# combined.net
KiCad netlist of a schematic drawn in EAGLE
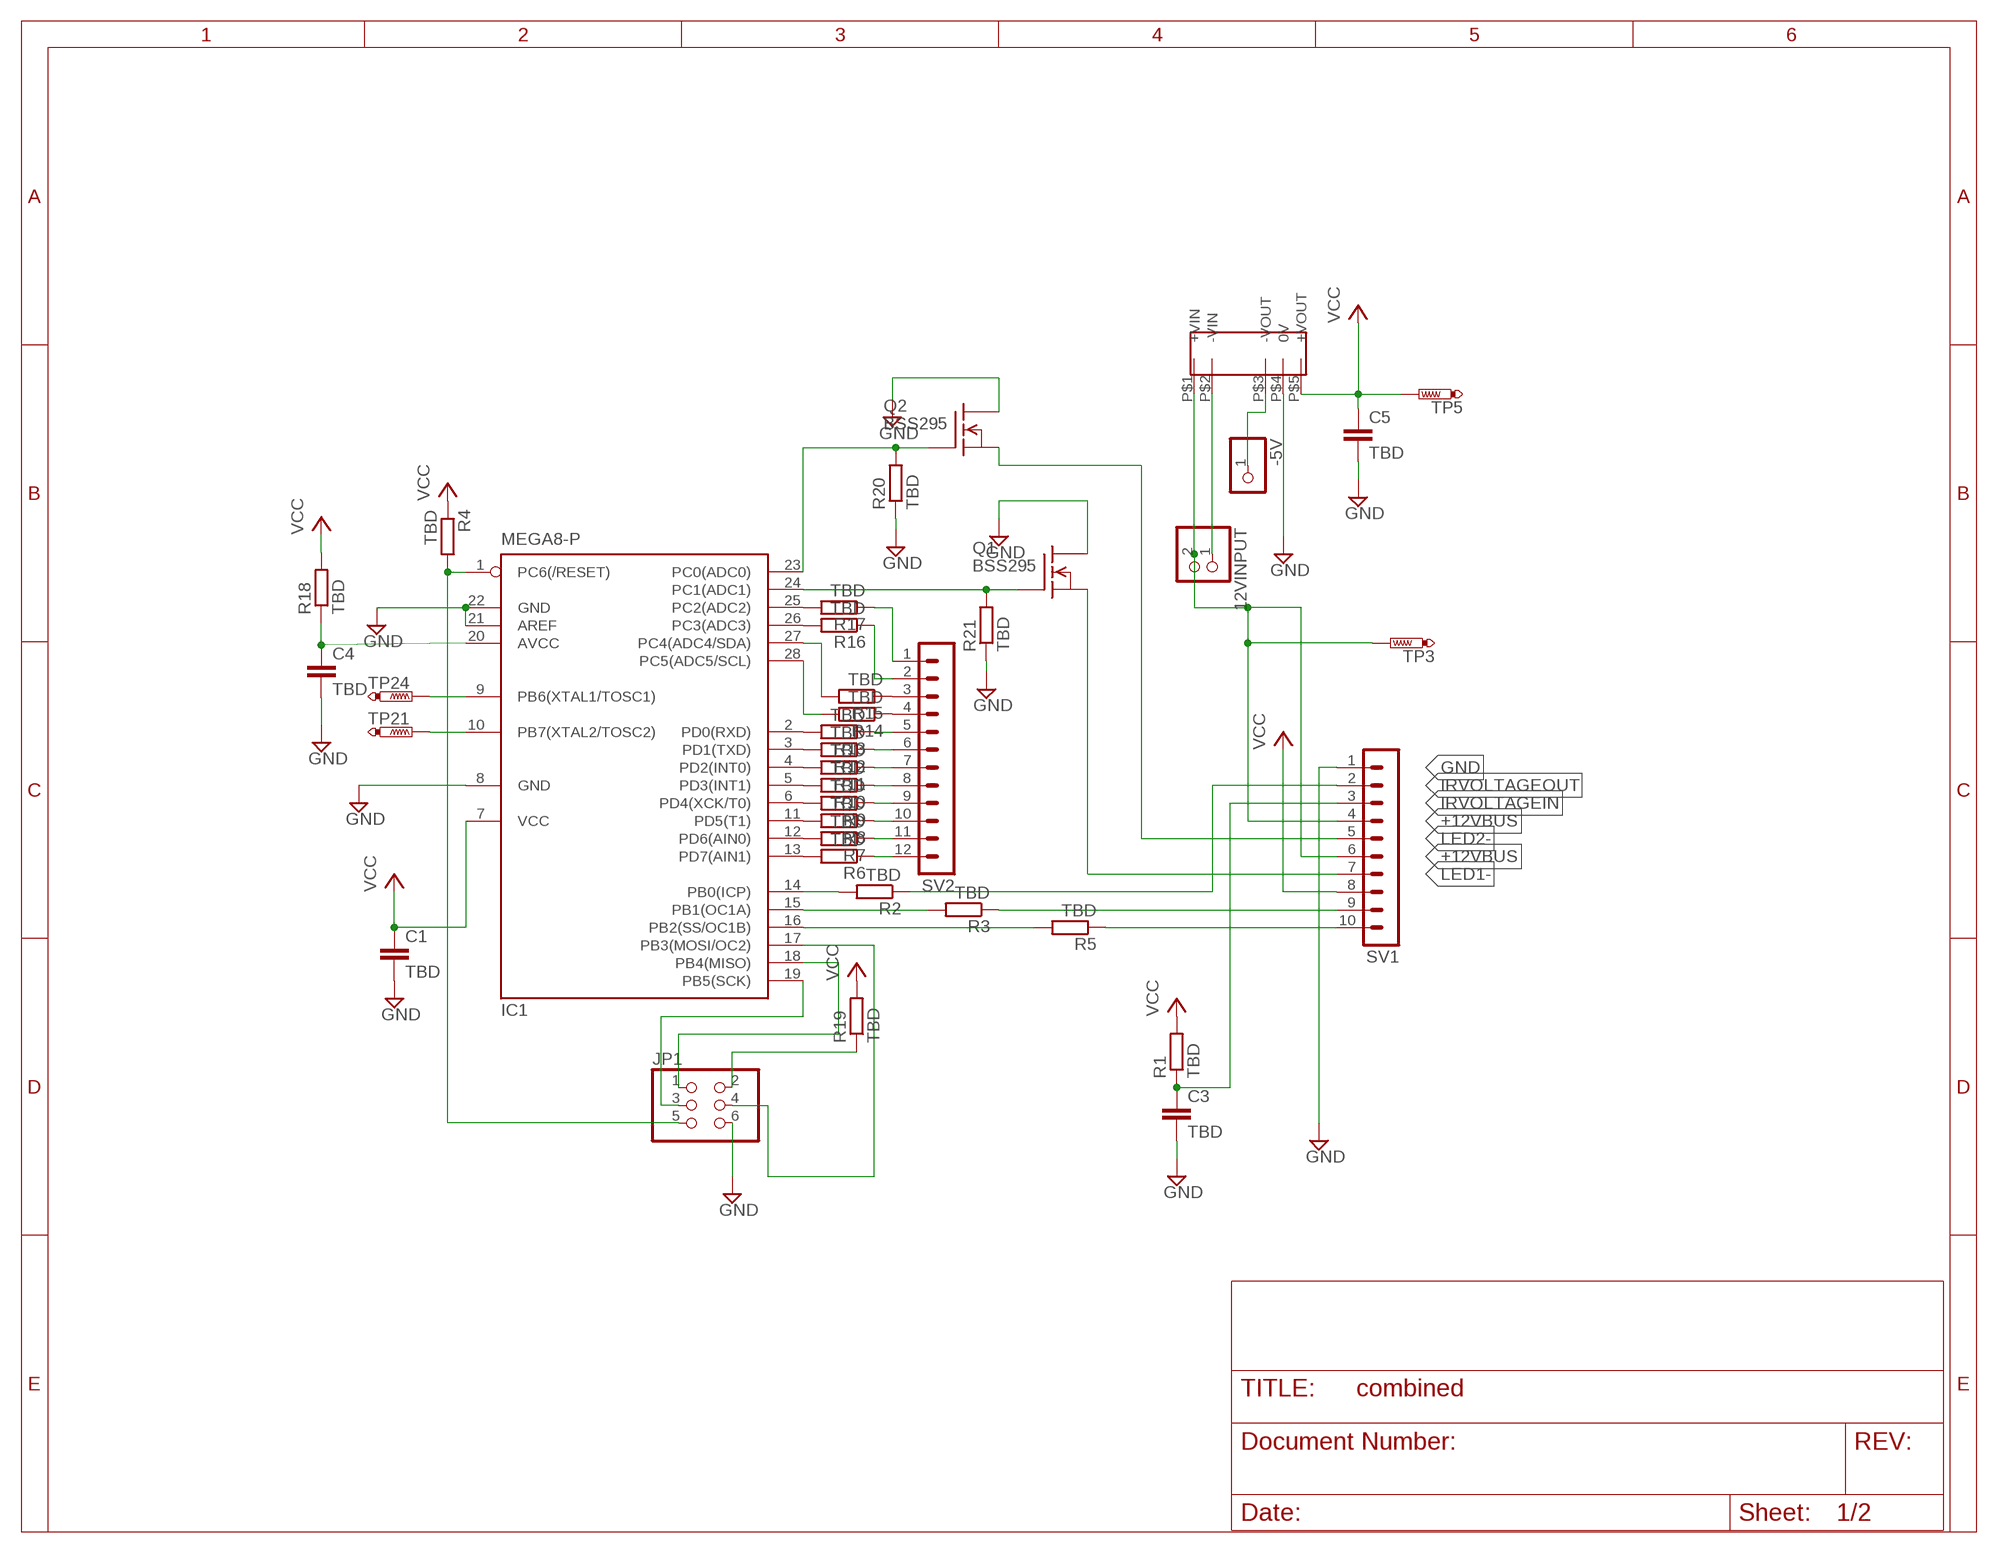
[diagram p0: schematic, sheet 1]
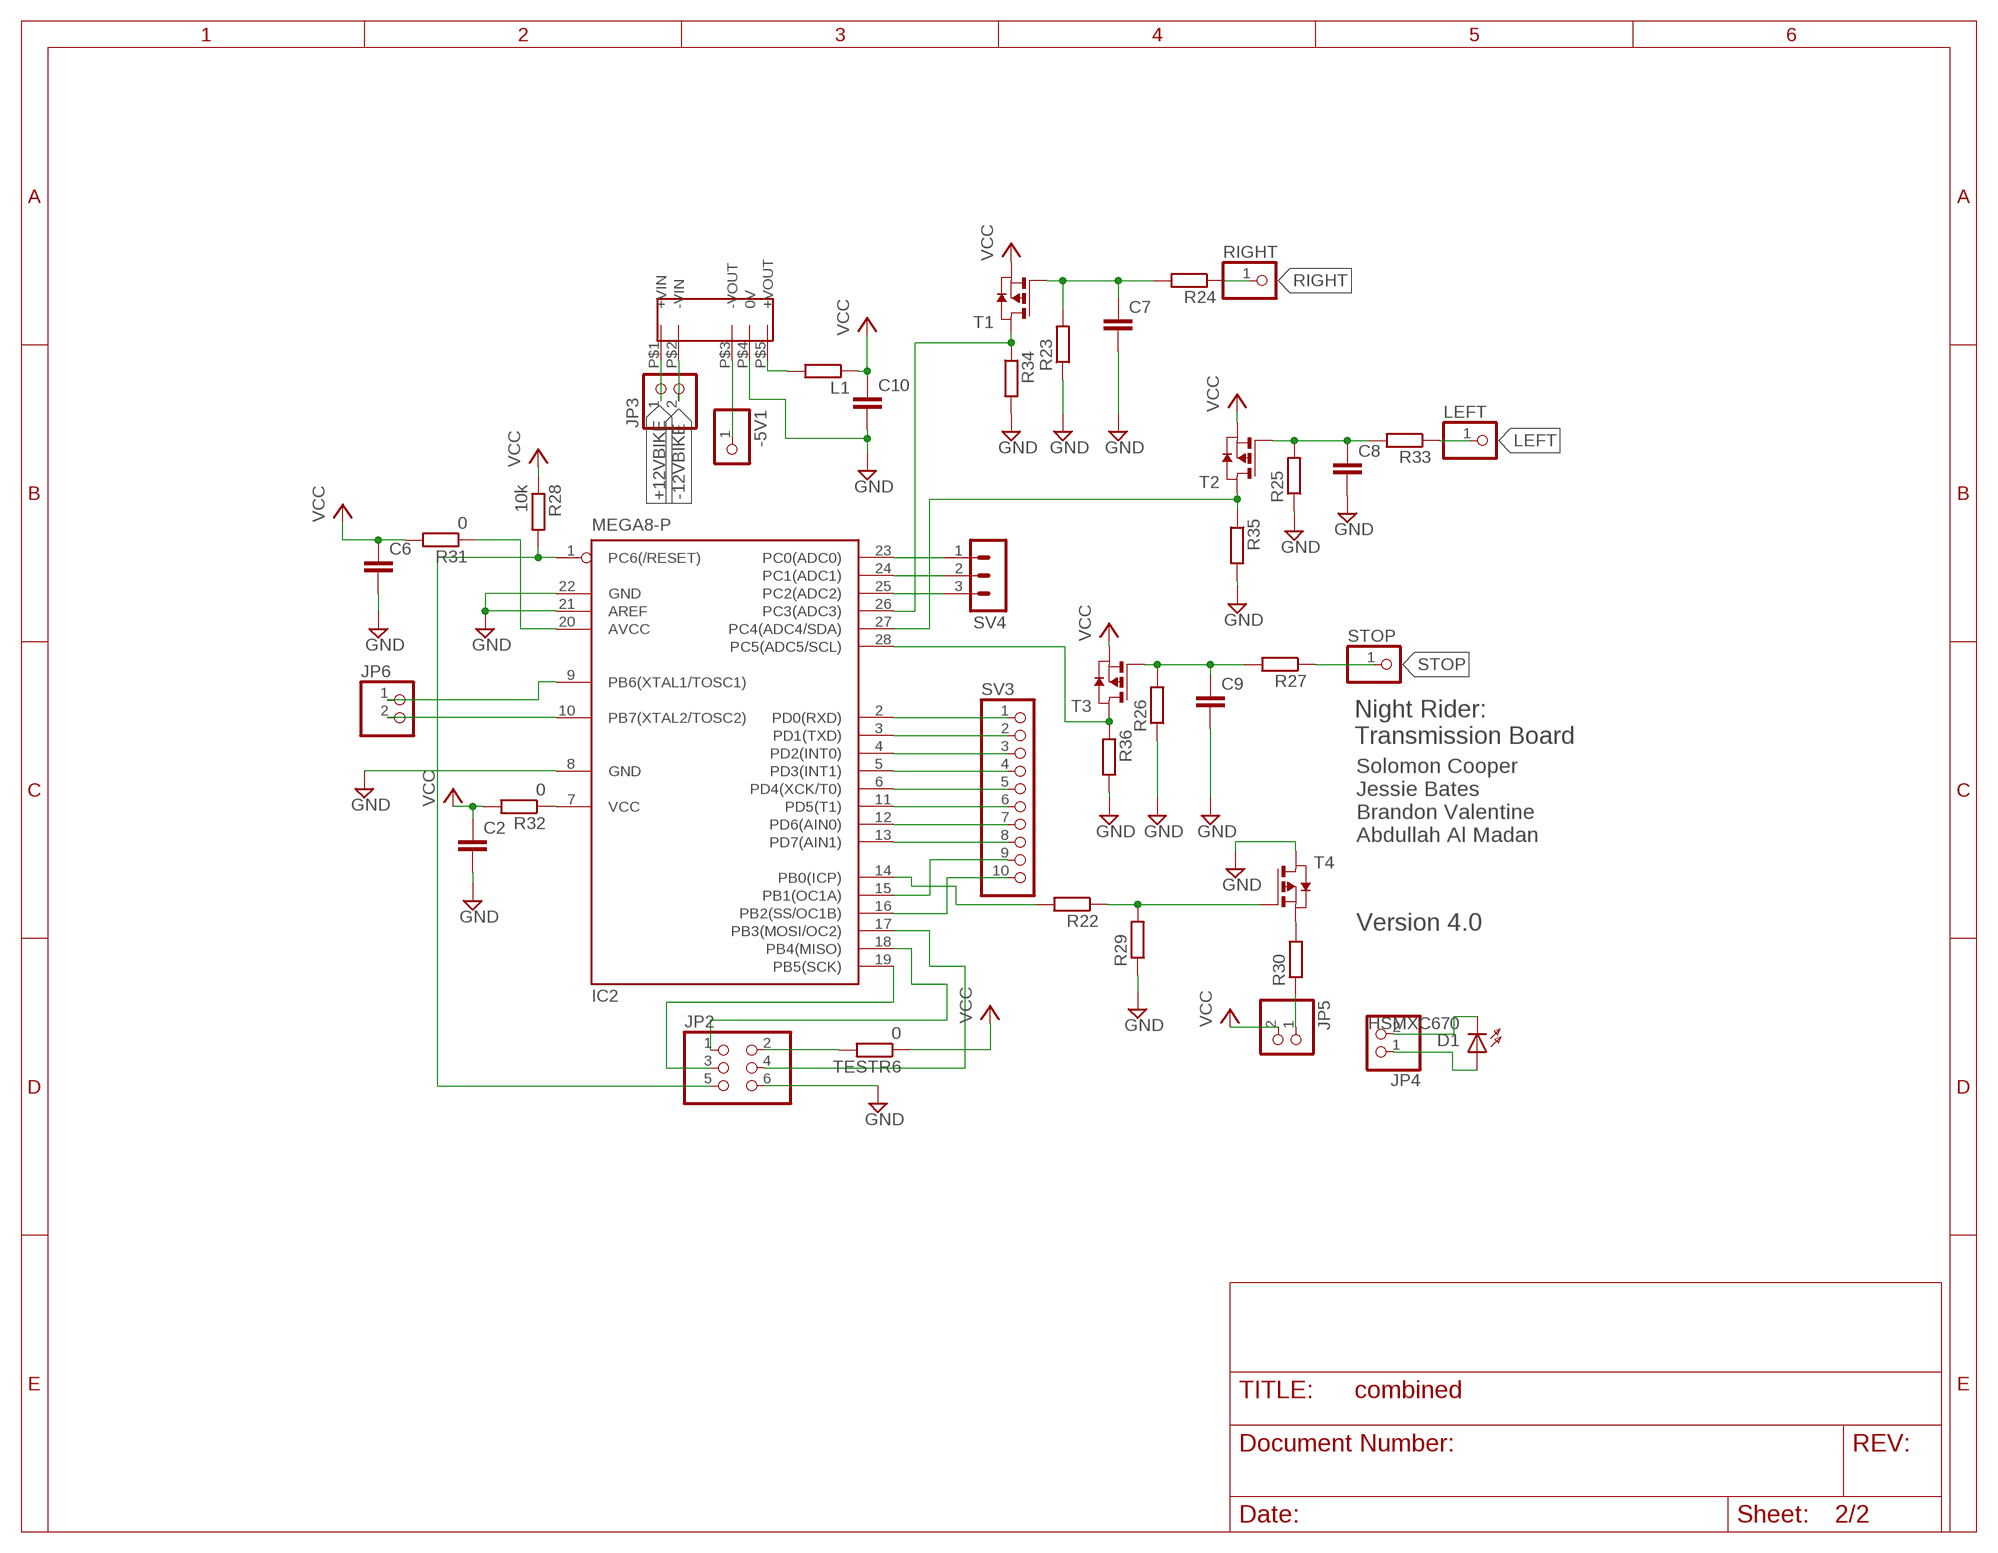
[diagram p1: schematic, sheet 2]

(export (version "E")
  (design (tool "Eeschema 10.0.6"))
  (components
    (comp (ref "-5V1")
      (value "PINHD-1X1")
      (footprint "eagle-import:1X01")
      (libsource (lib "eagle-import") (part "PINHD-1X1"))
    )
    (comp (ref "C2")
      (value "C-EUC0805")
      (footprint "eagle-import:C0805")
      (libsource (lib "eagle-import") (part "C-EUC0805"))
    )
    (comp (ref "C6")
      (value "C-EUC0805")
      (footprint "eagle-import:C0805")
      (libsource (lib "eagle-import") (part "C-EUC0805"))
    )
    (comp (ref "C7")
      (value "C-EUC0805")
      (footprint "eagle-import:C0805")
      (libsource (lib "eagle-import") (part "C-EUC0805"))
    )
    (comp (ref "C8")
      (value "C-EUC0805")
      (footprint "eagle-import:C0805")
      (libsource (lib "eagle-import") (part "C-EUC0805"))
    )
    (comp (ref "C9")
      (value "C-EUC0805")
      (footprint "eagle-import:C0805")
      (libsource (lib "eagle-import") (part "C-EUC0805"))
    )
    (comp (ref "C10")
      (value "C-EUC0805")
      (footprint "eagle-import:C0805")
      (libsource (lib "eagle-import") (part "C-EUC0805"))
    )
    (comp (ref "D1")
      (value "HSMXC670")
      (footprint "eagle-import:HSMXC670")
      (fields (field (name "OC_FARNELL") "unknown") (field (name "OC_NEWARK") "unknown"))
      (libsource (lib "eagle-import") (part "HSMXC670"))
    )
    (comp (ref "IC2")
      (value "MEGA8-P")
      (footprint "eagle-import:DIL28-3")
      (libsource (lib "eagle-import") (part "MEGA8-P"))
    )
    (comp (ref "JP2")
      (value "PINHD-2X3")
      (footprint "eagle-import:2X03")
      (libsource (lib "eagle-import") (part "PINHD-2X3"))
    )
    (comp (ref "JP3")
      (value "PINHD-1X2")
      (footprint "eagle-import:1X02")
      (libsource (lib "eagle-import") (part "PINHD-1X2"))
    )
    (comp (ref "JP4")
      (value "PINHD-1X2")
      (footprint "eagle-import:1X02")
      (libsource (lib "eagle-import") (part "PINHD-1X2"))
    )
    (comp (ref "JP5")
      (value "PINHD-1X2")
      (footprint "eagle-import:1X02")
      (libsource (lib "eagle-import") (part "PINHD-1X2"))
    )
    (comp (ref "JP6")
      (value "PINHD-1X2")
      (footprint "eagle-import:1X02")
      (libsource (lib "eagle-import") (part "PINHD-1X2"))
    )
    (comp (ref "L1")
      (value "R-EU_M0805")
      (footprint "eagle-import:M0805")
      (libsource (lib "eagle-import") (part "R-EU_M0805"))
    )
    (comp (ref "LEFT")
      (value "PINHD-1X1")
      (footprint "eagle-import:1X01")
      (libsource (lib "eagle-import") (part "PINHD-1X1"))
    )
    (comp (ref "R22")
      (value "R-EU_M0805")
      (footprint "eagle-import:M0805")
      (libsource (lib "eagle-import") (part "R-EU_M0805"))
    )
    (comp (ref "R23")
      (value "R-EU_M0805")
      (footprint "eagle-import:M0805")
      (libsource (lib "eagle-import") (part "R-EU_M0805"))
    )
    (comp (ref "R24")
      (value "R-EU_M0805")
      (footprint "eagle-import:M0805")
      (libsource (lib "eagle-import") (part "R-EU_M0805"))
    )
    (comp (ref "R25")
      (value "R-EU_M0805")
      (footprint "eagle-import:M0805")
      (libsource (lib "eagle-import") (part "R-EU_M0805"))
    )
    (comp (ref "R26")
      (value "R-EU_M0805")
      (footprint "eagle-import:M0805")
      (libsource (lib "eagle-import") (part "R-EU_M0805"))
    )
    (comp (ref "R27")
      (value "R-EU_M0805")
      (footprint "eagle-import:M0805")
      (libsource (lib "eagle-import") (part "R-EU_M0805"))
    )
    (comp (ref "R28")
      (value "10k")
      (footprint "eagle-import:M0805")
      (libsource (lib "eagle-import") (part "R-EU_M0805"))
    )
    (comp (ref "R29")
      (value "R-EU_M0805")
      (footprint "eagle-import:M0805")
      (libsource (lib "eagle-import") (part "R-EU_M0805"))
    )
    (comp (ref "R30")
      (value "R-EU_M0805")
      (footprint "eagle-import:M0805")
      (libsource (lib "eagle-import") (part "R-EU_M0805"))
    )
    (comp (ref "R31")
      (value "0")
      (footprint "eagle-import:M0805")
      (libsource (lib "eagle-import") (part "R-EU_M0805"))
    )
    (comp (ref "R32")
      (value "0")
      (footprint "eagle-import:M0805")
      (libsource (lib "eagle-import") (part "R-EU_M0805"))
    )
    (comp (ref "R33")
      (value "R-EU_M0805")
      (footprint "eagle-import:M0805")
      (libsource (lib "eagle-import") (part "R-EU_M0805"))
    )
    (comp (ref "R34")
      (value "R-EU_M0805")
      (footprint "eagle-import:M0805")
      (libsource (lib "eagle-import") (part "R-EU_M0805"))
    )
    (comp (ref "R35")
      (value "R-EU_M0805")
      (footprint "eagle-import:M0805")
      (libsource (lib "eagle-import") (part "R-EU_M0805"))
    )
    (comp (ref "R36")
      (value "R-EU_M0805")
      (footprint "eagle-import:M0805")
      (libsource (lib "eagle-import") (part "R-EU_M0805"))
    )
    (comp (ref "RIGHT")
      (value "PINHD-1X1")
      (footprint "eagle-import:1X01")
      (libsource (lib "eagle-import") (part "PINHD-1X1"))
    )
    (comp (ref "STOP")
      (value "PINHD-1X1")
      (footprint "eagle-import:1X01")
      (libsource (lib "eagle-import") (part "PINHD-1X1"))
    )
    (comp (ref "SV3")
      (value "PINHD-1X10")
      (footprint "eagle-import:1X10")
      (libsource (lib "eagle-import") (part "PINHD-1X10"))
    )
    (comp (ref "SV4")
      (value "MA03-1")
      (footprint "eagle-import:MA03-1")
      (libsource (lib "eagle-import") (part "MA03-1"))
    )
    (comp (ref "T1")
      (value "PMOSSOT23")
      (footprint "eagle-import:SOT-23")
      (fields (field (name "OC_FARNELL") "unknown") (field (name "OC_NEWARK") "unknown"))
      (libsource (lib "eagle-import") (part "PMOSSOT23"))
    )
    (comp (ref "T2")
      (value "PMOSSOT23")
      (footprint "eagle-import:SOT-23")
      (libsource (lib "eagle-import") (part "PMOSSOT23"))
    )
    (comp (ref "T3")
      (value "PMOSSOT23")
      (footprint "eagle-import:SOT-23")
      (libsource (lib "eagle-import") (part "PMOSSOT23"))
    )
    (comp (ref "T4")
      (value "PMOSSOT23")
      (footprint "eagle-import:SOT-23")
      (fields (field (name "OC_FARNELL") "unknown") (field (name "OC_NEWARK") "unknown"))
      (libsource (lib "eagle-import") (part "PMOSSOT23"))
    )
    (comp (ref "TESTR6")
      (value "0")
      (footprint "eagle-import:M0805")
      (libsource (lib "eagle-import") (part "R-EU_M0805"))
    )
    (comp (ref "U$2")
      (value "NKA1205SC")
      (footprint "eagle-import:NKA1205SC")
      (libsource (lib "eagle-import") (part "NKA1205SC"))
    )
    (comp (ref "-5V")
      (value "PINHD-1X1")
      (footprint "eagle-import:1X01")
      (libsource (lib "eagle-import") (part "PINHD-1X1"))
    )
    (comp (ref "12VINPUT")
      (value "PINHD-1X2")
      (footprint "eagle-import:1X02")
      (libsource (lib "eagle-import") (part "PINHD-1X2"))
    )
    (comp (ref "C1")
      (value "TBD")
      (footprint "eagle-import:C0805")
      (libsource (lib "eagle-import") (part "C-EUC0805"))
    )
    (comp (ref "C3")
      (value "TBD")
      (footprint "eagle-import:C0805")
      (libsource (lib "eagle-import") (part "C-EUC0805"))
    )
    (comp (ref "C4")
      (value "TBD")
      (footprint "eagle-import:C0805")
      (libsource (lib "eagle-import") (part "C-EUC0805"))
    )
    (comp (ref "C5")
      (value "TBD")
      (footprint "eagle-import:C0805")
      (libsource (lib "eagle-import") (part "C-EUC0805"))
    )
    (comp (ref "IC1")
      (value "MEGA8-P")
      (footprint "eagle-import:DIL28-3")
      (libsource (lib "eagle-import") (part "MEGA8-P"))
    )
    (comp (ref "JP1")
      (value "PINHD-2X3")
      (footprint "eagle-import:2X03")
      (libsource (lib "eagle-import") (part "PINHD-2X3"))
    )
    (comp (ref "Q1")
      (value "BSS295")
      (footprint "eagle-import:TO92")
      (libsource (lib "eagle-import") (part "BSS295"))
    )
    (comp (ref "Q2")
      (value "BSS295")
      (footprint "eagle-import:TO92")
      (libsource (lib "eagle-import") (part "BSS295"))
    )
    (comp (ref "R1")
      (value "TBD")
      (footprint "eagle-import:R0805")
      (libsource (lib "eagle-import") (part "R-EU_R0805"))
    )
    (comp (ref "R2")
      (value "TBD")
      (footprint "eagle-import:R0805")
      (libsource (lib "eagle-import") (part "R-EU_R0805"))
    )
    (comp (ref "R3")
      (value "TBD")
      (footprint "eagle-import:R0805")
      (libsource (lib "eagle-import") (part "R-EU_R0805"))
    )
    (comp (ref "R4")
      (value "TBD")
      (footprint "eagle-import:R0805")
      (libsource (lib "eagle-import") (part "R-EU_R0805"))
    )
    (comp (ref "R5")
      (value "TBD")
      (footprint "eagle-import:R0805")
      (libsource (lib "eagle-import") (part "R-EU_R0805"))
    )
    (comp (ref "R6")
      (value "TBD")
      (footprint "eagle-import:R0805")
      (libsource (lib "eagle-import") (part "R-EU_R0805"))
    )
    (comp (ref "R7")
      (value "TBD")
      (footprint "eagle-import:R0805")
      (libsource (lib "eagle-import") (part "R-EU_R0805"))
    )
    (comp (ref "R8")
      (value "TBD")
      (footprint "eagle-import:R0805")
      (libsource (lib "eagle-import") (part "R-EU_R0805"))
    )
    (comp (ref "R9")
      (value "TBD")
      (footprint "eagle-import:R0805")
      (libsource (lib "eagle-import") (part "R-EU_R0805"))
    )
    (comp (ref "R10")
      (value "TBD")
      (footprint "eagle-import:R0805")
      (libsource (lib "eagle-import") (part "R-EU_R0805"))
    )
    (comp (ref "R11")
      (value "TBD")
      (footprint "eagle-import:R0805")
      (libsource (lib "eagle-import") (part "R-EU_R0805"))
    )
    (comp (ref "R12")
      (value "TBD")
      (footprint "eagle-import:R0805")
      (libsource (lib "eagle-import") (part "R-EU_R0805"))
    )
    (comp (ref "R13")
      (value "TBD")
      (footprint "eagle-import:R0805")
      (libsource (lib "eagle-import") (part "R-EU_R0805"))
    )
    (comp (ref "R14")
      (value "TBD")
      (footprint "eagle-import:R0805")
      (libsource (lib "eagle-import") (part "R-EU_R0805"))
    )
    (comp (ref "R15")
      (value "TBD")
      (footprint "eagle-import:R0805")
      (libsource (lib "eagle-import") (part "R-EU_R0805"))
    )
    (comp (ref "R16")
      (value "TBD")
      (footprint "eagle-import:R0805")
      (libsource (lib "eagle-import") (part "R-EU_R0805"))
    )
    (comp (ref "R17")
      (value "TBD")
      (footprint "eagle-import:R0805")
      (libsource (lib "eagle-import") (part "R-EU_R0805"))
    )
    (comp (ref "R18")
      (value "TBD")
      (footprint "eagle-import:R0805")
      (libsource (lib "eagle-import") (part "R-EU_R0805"))
    )
    (comp (ref "R19")
      (value "TBD")
      (footprint "eagle-import:R0805")
      (libsource (lib "eagle-import") (part "R-EU_R0805"))
    )
    (comp (ref "R20")
      (value "TBD")
      (footprint "eagle-import:R0805")
      (libsource (lib "eagle-import") (part "R-EU_R0805"))
    )
    (comp (ref "R21")
      (value "TBD")
      (footprint "eagle-import:R0805")
      (libsource (lib "eagle-import") (part "R-EU_R0805"))
    )
    (comp (ref "SV1")
      (value "MA10-1")
      (footprint "eagle-import:MA10-1")
      (libsource (lib "eagle-import") (part "MA10-1"))
    )
    (comp (ref "SV2")
      (value "MA12-1")
      (footprint "eagle-import:MA12-1")
      (libsource (lib "eagle-import") (part "MA12-1"))
    )
    (comp (ref "TP3")
      (value "PTR1B1,27")
      (footprint "eagle-import:B1,27")
      (libsource (lib "eagle-import") (part "PTR1B1,27"))
    )
    (comp (ref "TP5")
      (value "PTR1B1,27")
      (footprint "eagle-import:B1,27")
      (libsource (lib "eagle-import") (part "PTR1B1,27"))
    )
    (comp (ref "TP21")
      (value "PTR1B1,27")
      (footprint "eagle-import:B1,27")
      (libsource (lib "eagle-import") (part "PTR1B1,27"))
    )
    (comp (ref "TP24")
      (value "PTR1B1,27")
      (footprint "eagle-import:B1,27")
      (libsource (lib "eagle-import") (part "PTR1B1,27"))
    )
    (comp (ref "U$1")
      (value "NKA1205SC")
      (footprint "eagle-import:NKA1205SC")
      (libsource (lib "eagle-import") (part "NKA1205SC"))
    )
  )
  (nets
    (net (code "1") (name "+12VBIKE") (class "Default")
      (node (ref "JP3") (pin "1") (pinfunction "1_1") (pintype "passive"))
      (node (ref "U$2") (pin "P$1") (pinfunction "+VIN_P$1") (pintype "bidirectional"))
    )
    (net (code "2") (name "+12VBUS") (class "Default")
      (node (ref "12VINPUT") (pin "2") (pinfunction "2_2") (pintype "passive"))
      (node (ref "SV1") (pin "4") (pinfunction "4_4") (pintype "passive"))
      (node (ref "SV1") (pin "6") (pinfunction "6_6") (pintype "passive"))
      (node (ref "TP3") (pin "TP") (pinfunction "TP_TP") (pintype "input"))
      (node (ref "U$1") (pin "P$1") (pinfunction "+VIN_P$1") (pintype "bidirectional"))
    )
    (net (code "3") (name "-12VBIKE") (class "Default")
      (node (ref "JP3") (pin "2") (pinfunction "2_2") (pintype "passive"))
      (node (ref "U$2") (pin "P$2") (pinfunction "-VIN_P$2") (pintype "bidirectional"))
    )
    (net (code "4") (name "GND") (class "Default")
      (node (ref "C1") (pin "2") (pinfunction "2_2") (pintype "passive"))
      (node (ref "C10") (pin "2") (pinfunction "2_2") (pintype "passive"))
      (node (ref "C2") (pin "2") (pinfunction "2_2") (pintype "passive"))
      (node (ref "C3") (pin "2") (pinfunction "2_2") (pintype "passive"))
      (node (ref "C4") (pin "2") (pinfunction "2_2") (pintype "passive"))
      (node (ref "C5") (pin "2") (pinfunction "2_2") (pintype "passive"))
      (node (ref "C6") (pin "2") (pinfunction "2_2") (pintype "passive"))
      (node (ref "C7") (pin "2") (pinfunction "2_2") (pintype "passive"))
      (node (ref "C8") (pin "2") (pinfunction "2_2") (pintype "passive"))
      (node (ref "C9") (pin "2") (pinfunction "2_2") (pintype "passive"))
      (node (ref "IC1") (pin "21") (pinfunction "AREF_21") (pintype "passive"))
      (node (ref "IC1") (pin "22") (pinfunction "GND_22") (pintype "power_in"))
      (node (ref "IC1") (pin "8") (pinfunction "GND_8") (pintype "power_in"))
      (node (ref "IC2") (pin "21") (pinfunction "AREF_21") (pintype "passive"))
      (node (ref "IC2") (pin "22") (pinfunction "GND_22") (pintype "power_in"))
      (node (ref "IC2") (pin "8") (pinfunction "GND_8") (pintype "power_in"))
      (node (ref "JP1") (pin "6") (pinfunction "6_6") (pintype "passive"))
      (node (ref "JP2") (pin "6") (pinfunction "6_6") (pintype "passive"))
      (node (ref "Q1") (pin "2") (pinfunction "D_2") (pintype "passive"))
      (node (ref "Q2") (pin "2") (pinfunction "D_2") (pintype "passive"))
      (node (ref "R20") (pin "1") (pinfunction "1_1") (pintype "passive"))
      (node (ref "R21") (pin "1") (pinfunction "1_1") (pintype "passive"))
      (node (ref "R23") (pin "1") (pinfunction "1_1") (pintype "passive"))
      (node (ref "R25") (pin "1") (pinfunction "1_1") (pintype "passive"))
      (node (ref "R26") (pin "1") (pinfunction "1_1") (pintype "passive"))
      (node (ref "R29") (pin "1") (pinfunction "1_1") (pintype "passive"))
      (node (ref "R34") (pin "2") (pinfunction "2_2") (pintype "passive"))
      (node (ref "R35") (pin "2") (pinfunction "2_2") (pintype "passive"))
      (node (ref "R36") (pin "2") (pinfunction "2_2") (pintype "passive"))
      (node (ref "SV1") (pin "1") (pinfunction "1_1") (pintype "passive"))
      (node (ref "T4") (pin "1") (pinfunction "D_1") (pintype "passive"))
      (node (ref "U$1") (pin "P$4") (pinfunction "0V_P$4") (pintype "bidirectional"))
      (node (ref "U$2") (pin "P$4") (pinfunction "0V_P$4") (pintype "bidirectional"))
    )
    (net (code "5") (name "IRVOLTAGEIN") (class "Default")
      (node (ref "C3") (pin "1") (pinfunction "1_1") (pintype "passive"))
      (node (ref "R1") (pin "1") (pinfunction "1_1") (pintype "passive"))
      (node (ref "SV1") (pin "3") (pinfunction "3_3") (pintype "passive"))
    )
    (net (code "6") (name "IRVOLTAGEOUT") (class "Default")
      (node (ref "R2") (pin "1") (pinfunction "1_1") (pintype "passive"))
      (node (ref "SV1") (pin "2") (pinfunction "2_2") (pintype "passive"))
    )
    (net (code "7") (name "LED1-") (class "Default")
      (node (ref "Q1") (pin "3") (pinfunction "S_3") (pintype "passive"))
      (node (ref "SV1") (pin "7") (pinfunction "7_7") (pintype "passive"))
    )
    (net (code "8") (name "LED2-") (class "Default")
      (node (ref "Q2") (pin "3") (pinfunction "S_3") (pintype "passive"))
      (node (ref "SV1") (pin "5") (pinfunction "5_5") (pintype "passive"))
    )
    (net (code "9") (name "LEFT") (class "Default")
      (node (ref "LEFT") (pin "1") (pinfunction "1_1") (pintype "passive"))
      (node (ref "R33") (pin "1") (pinfunction "1_1") (pintype "passive"))
    )
    (net (code "10") (name "Net-(D1-C)") (class "Default")
      (node (ref "D1") (pin "K") (pinfunction "C_K") (pintype "passive"))
      (node (ref "JP4") (pin "2") (pinfunction "2_2") (pintype "passive"))
    )
    (net (code "11") (name "Net-(D1-PadA)") (class "Default")
      (node (ref "D1") (pin "A") (pinfunction "A_A") (pintype "passive"))
      (node (ref "JP4") (pin "1") (pinfunction "1_1") (pintype "passive"))
    )
    (net (code "12") (name "Net-(IC1-AVCC)") (class "Default")
      (node (ref "C4") (pin "1") (pinfunction "1_1") (pintype "passive"))
      (node (ref "IC1") (pin "20") (pinfunction "AVCC_20") (pintype "power_in"))
      (node (ref "R18") (pin "1") (pinfunction "1_1") (pintype "passive"))
    )
    (net (code "13") (name "Net-(IC1-PB0(ICP))") (class "Default")
      (node (ref "IC1") (pin "14") (pinfunction "PB0(ICP)_14") (pintype "bidirectional"))
      (node (ref "R2") (pin "2") (pinfunction "2_2") (pintype "passive"))
    )
    (net (code "14") (name "Net-(IC1-PB1(OC1A))") (class "Default")
      (node (ref "IC1") (pin "15") (pinfunction "PB1(OC1A)_15") (pintype "bidirectional"))
      (node (ref "R3") (pin "2") (pinfunction "2_2") (pintype "passive"))
    )
    (net (code "15") (name "Net-(IC1-PB2(SS{slash}OC1B))") (class "Default")
      (node (ref "IC1") (pin "16") (pinfunction "PB2(SS/OC1B)_16") (pintype "bidirectional"))
      (node (ref "R5") (pin "2") (pinfunction "2_2") (pintype "passive"))
    )
    (net (code "16") (name "Net-(IC1-PB3(MOSI{slash}OC2))") (class "Default")
      (node (ref "IC1") (pin "17") (pinfunction "PB3(MOSI/OC2)_17") (pintype "bidirectional"))
      (node (ref "JP1") (pin "4") (pinfunction "4_4") (pintype "passive"))
    )
    (net (code "17") (name "Net-(IC1-PB4(MISO))") (class "Default")
      (node (ref "IC1") (pin "18") (pinfunction "PB4(MISO)_18") (pintype "bidirectional"))
      (node (ref "JP1") (pin "1") (pinfunction "1_1") (pintype "passive"))
    )
    (net (code "18") (name "Net-(IC1-PB5(SCK))") (class "Default")
      (node (ref "IC1") (pin "19") (pinfunction "PB5(SCK)_19") (pintype "bidirectional"))
      (node (ref "JP1") (pin "3") (pinfunction "3_3") (pintype "passive"))
    )
    (net (code "19") (name "Net-(IC1-PB6(XTAL1{slash}TOSC1))") (class "Default")
      (node (ref "IC1") (pin "9") (pinfunction "PB6(XTAL1/TOSC1)_9") (pintype "bidirectional"))
      (node (ref "TP24") (pin "TP") (pinfunction "TP_TP") (pintype "input"))
    )
    (net (code "20") (name "Net-(IC1-PB7(XTAL2{slash}TOSC2))") (class "Default")
      (node (ref "IC1") (pin "10") (pinfunction "PB7(XTAL2/TOSC2)_10") (pintype "bidirectional"))
      (node (ref "TP21") (pin "TP") (pinfunction "TP_TP") (pintype "input"))
    )
    (net (code "21") (name "Net-(IC1-PC0(ADC0))") (class "Default")
      (node (ref "IC1") (pin "23") (pinfunction "PC0(ADC0)_23") (pintype "bidirectional"))
      (node (ref "Q2") (pin "1") (pinfunction "G_1") (pintype "passive"))
      (node (ref "R20") (pin "2") (pinfunction "2_2") (pintype "passive"))
    )
    (net (code "22") (name "Net-(IC1-PC1(ADC1))") (class "Default")
      (node (ref "IC1") (pin "24") (pinfunction "PC1(ADC1)_24") (pintype "bidirectional"))
      (node (ref "Q1") (pin "1") (pinfunction "G_1") (pintype "passive"))
      (node (ref "R21") (pin "2") (pinfunction "2_2") (pintype "passive"))
    )
    (net (code "23") (name "Net-(IC1-PC2(ADC2))") (class "Default")
      (node (ref "IC1") (pin "25") (pinfunction "PC2(ADC2)_25") (pintype "bidirectional"))
      (node (ref "R17") (pin "2") (pinfunction "2_2") (pintype "passive"))
    )
    (net (code "24") (name "Net-(IC1-PC3(ADC3))") (class "Default")
      (node (ref "IC1") (pin "26") (pinfunction "PC3(ADC3)_26") (pintype "bidirectional"))
      (node (ref "R16") (pin "2") (pinfunction "2_2") (pintype "passive"))
    )
    (net (code "25") (name "Net-(IC1-PC4(ADC4{slash}SDA))") (class "Default")
      (node (ref "IC1") (pin "27") (pinfunction "PC4(ADC4/SDA)_27") (pintype "bidirectional"))
      (node (ref "R15") (pin "2") (pinfunction "2_2") (pintype "passive"))
    )
    (net (code "26") (name "Net-(IC1-PC5(ADC5{slash}SCL))") (class "Default")
      (node (ref "IC1") (pin "28") (pinfunction "PC5(ADC5/SCL)_28") (pintype "bidirectional"))
      (node (ref "R14") (pin "2") (pinfunction "2_2") (pintype "passive"))
    )
    (net (code "27") (name "Net-(IC1-PC6({slash}RESET))") (class "Default")
      (node (ref "IC1") (pin "1") (pinfunction "PC6(/RESET)_1") (pintype "bidirectional"))
      (node (ref "JP1") (pin "5") (pinfunction "5_5") (pintype "passive"))
      (node (ref "R4") (pin "2") (pinfunction "2_2") (pintype "passive"))
    )
    (net (code "28") (name "Net-(IC1-PD0(RXD))") (class "Default")
      (node (ref "IC1") (pin "2") (pinfunction "PD0(RXD)_2") (pintype "bidirectional"))
      (node (ref "R13") (pin "2") (pinfunction "2_2") (pintype "passive"))
    )
    (net (code "29") (name "Net-(IC1-PD1(TXD))") (class "Default")
      (node (ref "IC1") (pin "3") (pinfunction "PD1(TXD)_3") (pintype "bidirectional"))
      (node (ref "R12") (pin "2") (pinfunction "2_2") (pintype "passive"))
    )
    (net (code "30") (name "Net-(IC1-PD2(INT0))") (class "Default")
      (node (ref "IC1") (pin "4") (pinfunction "PD2(INT0)_4") (pintype "bidirectional"))
      (node (ref "R11") (pin "2") (pinfunction "2_2") (pintype "passive"))
    )
    (net (code "31") (name "Net-(IC1-PD3(INT1))") (class "Default")
      (node (ref "IC1") (pin "5") (pinfunction "PD3(INT1)_5") (pintype "bidirectional"))
      (node (ref "R10") (pin "2") (pinfunction "2_2") (pintype "passive"))
    )
    (net (code "32") (name "Net-(IC1-PD4(XCK{slash}T0))") (class "Default")
      (node (ref "IC1") (pin "6") (pinfunction "PD4(XCK/T0)_6") (pintype "bidirectional"))
      (node (ref "R9") (pin "2") (pinfunction "2_2") (pintype "passive"))
    )
    (net (code "33") (name "Net-(IC1-PD5(T1))") (class "Default")
      (node (ref "IC1") (pin "11") (pinfunction "PD5(T1)_11") (pintype "bidirectional"))
      (node (ref "R8") (pin "2") (pinfunction "2_2") (pintype "passive"))
    )
    (net (code "34") (name "Net-(IC1-PD6(AIN0))") (class "Default")
      (node (ref "IC1") (pin "12") (pinfunction "PD6(AIN0)_12") (pintype "bidirectional"))
      (node (ref "R7") (pin "2") (pinfunction "2_2") (pintype "passive"))
    )
    (net (code "35") (name "Net-(IC1-PD7(AIN1))") (class "Default")
      (node (ref "IC1") (pin "13") (pinfunction "PD7(AIN1)_13") (pintype "bidirectional"))
      (node (ref "R6") (pin "2") (pinfunction "2_2") (pintype "passive"))
    )
    (net (code "36") (name "Net-(IC2-AVCC)") (class "Default")
      (node (ref "IC2") (pin "20") (pinfunction "AVCC_20") (pintype "power_in"))
      (node (ref "R31") (pin "1") (pinfunction "1_1") (pintype "passive"))
    )
    (net (code "37") (name "Net-(IC2-PB0(ICP))") (class "Default")
      (node (ref "IC2") (pin "14") (pinfunction "PB0(ICP)_14") (pintype "bidirectional"))
      (node (ref "R22") (pin "2") (pinfunction "2_2") (pintype "passive"))
    )
    (net (code "38") (name "Net-(IC2-PB1(OC1A))") (class "Default")
      (node (ref "IC2") (pin "15") (pinfunction "PB1(OC1A)_15") (pintype "bidirectional"))
      (node (ref "SV3") (pin "9") (pinfunction "9_9") (pintype "passive"))
    )
    (net (code "39") (name "Net-(IC2-PB2(SS{slash}OC1B))") (class "Default")
      (node (ref "IC2") (pin "16") (pinfunction "PB2(SS/OC1B)_16") (pintype "bidirectional"))
      (node (ref "SV3") (pin "10") (pinfunction "10_10") (pintype "passive"))
    )
    (net (code "40") (name "Net-(IC2-PB3(MOSI{slash}OC2))") (class "Default")
      (node (ref "IC2") (pin "17") (pinfunction "PB3(MOSI/OC2)_17") (pintype "bidirectional"))
      (node (ref "JP2") (pin "4") (pinfunction "4_4") (pintype "passive"))
    )
    (net (code "41") (name "Net-(IC2-PB4(MISO))") (class "Default")
      (node (ref "IC2") (pin "18") (pinfunction "PB4(MISO)_18") (pintype "bidirectional"))
      (node (ref "JP2") (pin "1") (pinfunction "1_1") (pintype "passive"))
    )
    (net (code "42") (name "Net-(IC2-PB5(SCK))") (class "Default")
      (node (ref "IC2") (pin "19") (pinfunction "PB5(SCK)_19") (pintype "bidirectional"))
      (node (ref "JP2") (pin "3") (pinfunction "3_3") (pintype "passive"))
    )
    (net (code "43") (name "Net-(IC2-PB6(XTAL1{slash}TOSC1))") (class "Default")
      (node (ref "IC2") (pin "9") (pinfunction "PB6(XTAL1/TOSC1)_9") (pintype "bidirectional"))
      (node (ref "JP6") (pin "1") (pinfunction "1_1") (pintype "passive"))
    )
    (net (code "44") (name "Net-(IC2-PB7(XTAL2{slash}TOSC2))") (class "Default")
      (node (ref "IC2") (pin "10") (pinfunction "PB7(XTAL2/TOSC2)_10") (pintype "bidirectional"))
      (node (ref "JP6") (pin "2") (pinfunction "2_2") (pintype "passive"))
    )
    (net (code "45") (name "Net-(IC2-PC0(ADC0))") (class "Default")
      (node (ref "IC2") (pin "23") (pinfunction "PC0(ADC0)_23") (pintype "bidirectional"))
      (node (ref "SV4") (pin "1") (pinfunction "1_1") (pintype "passive"))
    )
    (net (code "46") (name "Net-(IC2-PC1(ADC1))") (class "Default")
      (node (ref "IC2") (pin "24") (pinfunction "PC1(ADC1)_24") (pintype "bidirectional"))
      (node (ref "SV4") (pin "2") (pinfunction "2_2") (pintype "passive"))
    )
    (net (code "47") (name "Net-(IC2-PC2(ADC2))") (class "Default")
      (node (ref "IC2") (pin "25") (pinfunction "PC2(ADC2)_25") (pintype "bidirectional"))
      (node (ref "SV4") (pin "3") (pinfunction "3_3") (pintype "passive"))
    )
    (net (code "48") (name "Net-(IC2-PC3(ADC3))") (class "Default")
      (node (ref "IC2") (pin "26") (pinfunction "PC3(ADC3)_26") (pintype "bidirectional"))
      (node (ref "R34") (pin "1") (pinfunction "1_1") (pintype "passive"))
      (node (ref "T1") (pin "1") (pinfunction "D_1") (pintype "passive"))
    )
    (net (code "49") (name "Net-(IC2-PC4(ADC4{slash}SDA))") (class "Default")
      (node (ref "IC2") (pin "27") (pinfunction "PC4(ADC4/SDA)_27") (pintype "bidirectional"))
      (node (ref "R35") (pin "1") (pinfunction "1_1") (pintype "passive"))
      (node (ref "T2") (pin "1") (pinfunction "D_1") (pintype "passive"))
    )
    (net (code "50") (name "Net-(IC2-PC5(ADC5{slash}SCL))") (class "Default")
      (node (ref "IC2") (pin "28") (pinfunction "PC5(ADC5/SCL)_28") (pintype "bidirectional"))
      (node (ref "R36") (pin "1") (pinfunction "1_1") (pintype "passive"))
      (node (ref "T3") (pin "1") (pinfunction "D_1") (pintype "passive"))
    )
    (net (code "51") (name "Net-(IC2-PC6({slash}RESET))") (class "Default")
      (node (ref "IC2") (pin "1") (pinfunction "PC6(/RESET)_1") (pintype "bidirectional"))
      (node (ref "JP2") (pin "5") (pinfunction "5_5") (pintype "passive"))
      (node (ref "R28") (pin "2") (pinfunction "2_2") (pintype "passive"))
    )
    (net (code "52") (name "Net-(IC2-PD0(RXD))") (class "Default")
      (node (ref "IC2") (pin "2") (pinfunction "PD0(RXD)_2") (pintype "bidirectional"))
      (node (ref "SV3") (pin "1") (pinfunction "1_1") (pintype "passive"))
    )
    (net (code "53") (name "Net-(IC2-PD1(TXD))") (class "Default")
      (node (ref "IC2") (pin "3") (pinfunction "PD1(TXD)_3") (pintype "bidirectional"))
      (node (ref "SV3") (pin "2") (pinfunction "2_2") (pintype "passive"))
    )
    (net (code "54") (name "Net-(IC2-PD2(INT0))") (class "Default")
      (node (ref "IC2") (pin "4") (pinfunction "PD2(INT0)_4") (pintype "bidirectional"))
      (node (ref "SV3") (pin "3") (pinfunction "3_3") (pintype "passive"))
    )
    (net (code "55") (name "Net-(IC2-PD3(INT1))") (class "Default")
      (node (ref "IC2") (pin "5") (pinfunction "PD3(INT1)_5") (pintype "bidirectional"))
      (node (ref "SV3") (pin "4") (pinfunction "4_4") (pintype "passive"))
    )
    (net (code "56") (name "Net-(IC2-PD4(XCK{slash}T0))") (class "Default")
      (node (ref "IC2") (pin "6") (pinfunction "PD4(XCK/T0)_6") (pintype "bidirectional"))
      (node (ref "SV3") (pin "5") (pinfunction "5_5") (pintype "passive"))
    )
    (net (code "57") (name "Net-(IC2-PD5(T1))") (class "Default")
      (node (ref "IC2") (pin "11") (pinfunction "PD5(T1)_11") (pintype "bidirectional"))
      (node (ref "SV3") (pin "6") (pinfunction "6_6") (pintype "passive"))
    )
    (net (code "58") (name "Net-(IC2-PD6(AIN0))") (class "Default")
      (node (ref "IC2") (pin "12") (pinfunction "PD6(AIN0)_12") (pintype "bidirectional"))
      (node (ref "SV3") (pin "7") (pinfunction "7_7") (pintype "passive"))
    )
    (net (code "59") (name "Net-(IC2-PD7(AIN1))") (class "Default")
      (node (ref "IC2") (pin "13") (pinfunction "PD7(AIN1)_13") (pintype "bidirectional"))
      (node (ref "SV3") (pin "8") (pinfunction "8_8") (pintype "passive"))
    )
    (net (code "60") (name "Net-(IC2-VCC)") (class "Default")
      (node (ref "IC2") (pin "7") (pinfunction "VCC_7") (pintype "power_in"))
      (node (ref "R32") (pin "1") (pinfunction "1_1") (pintype "passive"))
    )
    (net (code "61") (name "Net-(JP1-Pad2)") (class "Default")
      (node (ref "JP1") (pin "2") (pinfunction "2_2") (pintype "passive"))
      (node (ref "R19") (pin "1") (pinfunction "1_1") (pintype "passive"))
    )
    (net (code "62") (name "Net-(JP2-Pad2)") (class "Default")
      (node (ref "JP2") (pin "2") (pinfunction "2_2") (pintype "passive"))
      (node (ref "TESTR6") (pin "2") (pinfunction "2_2") (pintype "passive"))
    )
    (net (code "63") (name "Net-(JP5-Pad1)") (class "Default")
      (node (ref "JP5") (pin "1") (pinfunction "1_1") (pintype "passive"))
      (node (ref "R30") (pin "1") (pinfunction "1_1") (pintype "passive"))
    )
    (net (code "64") (name "Net-(R3-Pad1)") (class "Default")
      (node (ref "R3") (pin "1") (pinfunction "1_1") (pintype "passive"))
      (node (ref "SV1") (pin "9") (pinfunction "9_9") (pintype "passive"))
    )
    (net (code "65") (name "Net-(R5-Pad1)") (class "Default")
      (node (ref "R5") (pin "1") (pinfunction "1_1") (pintype "passive"))
      (node (ref "SV1") (pin "10") (pinfunction "10_10") (pintype "passive"))
    )
    (net (code "66") (name "Net-(R6-Pad1)") (class "Default")
      (node (ref "R6") (pin "1") (pinfunction "1_1") (pintype "passive"))
      (node (ref "SV2") (pin "12") (pinfunction "12_12") (pintype "passive"))
    )
    (net (code "67") (name "Net-(R7-Pad1)") (class "Default")
      (node (ref "R7") (pin "1") (pinfunction "1_1") (pintype "passive"))
      (node (ref "SV2") (pin "11") (pinfunction "11_11") (pintype "passive"))
    )
    (net (code "68") (name "Net-(R8-Pad1)") (class "Default")
      (node (ref "R8") (pin "1") (pinfunction "1_1") (pintype "passive"))
      (node (ref "SV2") (pin "10") (pinfunction "10_10") (pintype "passive"))
    )
    (net (code "69") (name "Net-(R9-Pad1)") (class "Default")
      (node (ref "R9") (pin "1") (pinfunction "1_1") (pintype "passive"))
      (node (ref "SV2") (pin "9") (pinfunction "9_9") (pintype "passive"))
    )
    (net (code "70") (name "Net-(R10-Pad1)") (class "Default")
      (node (ref "R10") (pin "1") (pinfunction "1_1") (pintype "passive"))
      (node (ref "SV2") (pin "8") (pinfunction "8_8") (pintype "passive"))
    )
    (net (code "71") (name "Net-(R11-Pad1)") (class "Default")
      (node (ref "R11") (pin "1") (pinfunction "1_1") (pintype "passive"))
      (node (ref "SV2") (pin "7") (pinfunction "7_7") (pintype "passive"))
    )
    (net (code "72") (name "Net-(R12-Pad1)") (class "Default")
      (node (ref "R12") (pin "1") (pinfunction "1_1") (pintype "passive"))
      (node (ref "SV2") (pin "6") (pinfunction "6_6") (pintype "passive"))
    )
    (net (code "73") (name "Net-(R13-Pad1)") (class "Default")
      (node (ref "R13") (pin "1") (pinfunction "1_1") (pintype "passive"))
      (node (ref "SV2") (pin "5") (pinfunction "5_5") (pintype "passive"))
    )
    (net (code "74") (name "Net-(R14-Pad1)") (class "Default")
      (node (ref "R14") (pin "1") (pinfunction "1_1") (pintype "passive"))
      (node (ref "SV2") (pin "4") (pinfunction "4_4") (pintype "passive"))
    )
    (net (code "75") (name "Net-(R15-Pad1)") (class "Default")
      (node (ref "R15") (pin "1") (pinfunction "1_1") (pintype "passive"))
      (node (ref "SV2") (pin "3") (pinfunction "3_3") (pintype "passive"))
    )
    (net (code "76") (name "Net-(R16-Pad1)") (class "Default")
      (node (ref "R16") (pin "1") (pinfunction "1_1") (pintype "passive"))
      (node (ref "SV2") (pin "2") (pinfunction "2_2") (pintype "passive"))
    )
    (net (code "77") (name "Net-(R17-Pad1)") (class "Default")
      (node (ref "R17") (pin "1") (pinfunction "1_1") (pintype "passive"))
      (node (ref "SV2") (pin "1") (pinfunction "1_1") (pintype "passive"))
    )
    (net (code "78") (name "Net-(T1-G)") (class "Default")
      (node (ref "C7") (pin "1") (pinfunction "1_1") (pintype "passive"))
      (node (ref "R23") (pin "2") (pinfunction "2_2") (pintype "passive"))
      (node (ref "R24") (pin "2") (pinfunction "2_2") (pintype "passive"))
      (node (ref "T1") (pin "3") (pinfunction "G_3") (pintype "passive"))
    )
    (net (code "79") (name "Net-(T2-G)") (class "Default")
      (node (ref "C8") (pin "1") (pinfunction "1_1") (pintype "passive"))
      (node (ref "R25") (pin "2") (pinfunction "2_2") (pintype "passive"))
      (node (ref "R33") (pin "2") (pinfunction "2_2") (pintype "passive"))
      (node (ref "T2") (pin "3") (pinfunction "G_3") (pintype "passive"))
    )
    (net (code "80") (name "Net-(T3-G)") (class "Default")
      (node (ref "C9") (pin "1") (pinfunction "1_1") (pintype "passive"))
      (node (ref "R26") (pin "2") (pinfunction "2_2") (pintype "passive"))
      (node (ref "R27") (pin "2") (pinfunction "2_2") (pintype "passive"))
      (node (ref "T3") (pin "3") (pinfunction "G_3") (pintype "passive"))
    )
    (net (code "81") (name "Net-(T4-G)") (class "Default")
      (node (ref "R22") (pin "1") (pinfunction "1_1") (pintype "passive"))
      (node (ref "R29") (pin "2") (pinfunction "2_2") (pintype "passive"))
      (node (ref "T4") (pin "3") (pinfunction "G_3") (pintype "passive"))
    )
    (net (code "82") (name "Net-(T4-S)") (class "Default")
      (node (ref "R30") (pin "2") (pinfunction "2_2") (pintype "passive"))
      (node (ref "T4") (pin "2") (pinfunction "S_2") (pintype "passive"))
    )
    (net (code "83") (name "Net-(U$1--VIN)") (class "Default")
      (node (ref "12VINPUT") (pin "1") (pinfunction "1_1") (pintype "passive"))
      (node (ref "U$1") (pin "P$2") (pinfunction "-VIN_P$2") (pintype "bidirectional"))
    )
    (net (code "84") (name "Net-(U$1--VOUT)") (class "Default")
      (node (ref "-5V") (pin "1") (pinfunction "1_1") (pintype "passive"))
      (node (ref "U$1") (pin "P$3") (pinfunction "-VOUT_P$3") (pintype "bidirectional"))
    )
    (net (code "85") (name "Net-(U$2-+VOUT)") (class "Default")
      (node (ref "L1") (pin "2") (pinfunction "2_2") (pintype "passive"))
      (node (ref "U$2") (pin "P$5") (pinfunction "+VOUT_P$5") (pintype "bidirectional"))
    )
    (net (code "86") (name "Net-(U$2--VOUT)") (class "Default")
      (node (ref "-5V1") (pin "1") (pinfunction "1_1") (pintype "passive"))
      (node (ref "U$2") (pin "P$3") (pinfunction "-VOUT_P$3") (pintype "bidirectional"))
    )
    (net (code "87") (name "RIGHT") (class "Default")
      (node (ref "R24") (pin "1") (pinfunction "1_1") (pintype "passive"))
      (node (ref "RIGHT") (pin "1") (pinfunction "1_1") (pintype "passive"))
    )
    (net (code "88") (name "STOP") (class "Default")
      (node (ref "R27") (pin "1") (pinfunction "1_1") (pintype "passive"))
      (node (ref "STOP") (pin "1") (pinfunction "1_1") (pintype "passive"))
    )
    (net (code "89") (name "VCC") (class "Default")
      (node (ref "C1") (pin "1") (pinfunction "1_1") (pintype "passive"))
      (node (ref "C10") (pin "1") (pinfunction "1_1") (pintype "passive"))
      (node (ref "C2") (pin "1") (pinfunction "1_1") (pintype "passive"))
      (node (ref "C5") (pin "1") (pinfunction "1_1") (pintype "passive"))
      (node (ref "C6") (pin "1") (pinfunction "1_1") (pintype "passive"))
      (node (ref "IC1") (pin "7") (pinfunction "VCC_7") (pintype "power_in"))
      (node (ref "JP5") (pin "2") (pinfunction "2_2") (pintype "passive"))
      (node (ref "L1") (pin "1") (pinfunction "1_1") (pintype "passive"))
      (node (ref "R1") (pin "2") (pinfunction "2_2") (pintype "passive"))
      (node (ref "R18") (pin "2") (pinfunction "2_2") (pintype "passive"))
      (node (ref "R19") (pin "2") (pinfunction "2_2") (pintype "passive"))
      (node (ref "R28") (pin "1") (pinfunction "1_1") (pintype "passive"))
      (node (ref "R31") (pin "2") (pinfunction "2_2") (pintype "passive"))
      (node (ref "R32") (pin "2") (pinfunction "2_2") (pintype "passive"))
      (node (ref "R4") (pin "1") (pinfunction "1_1") (pintype "passive"))
      (node (ref "SV1") (pin "8") (pinfunction "8_8") (pintype "passive"))
      (node (ref "T1") (pin "2") (pinfunction "S_2") (pintype "passive"))
      (node (ref "T2") (pin "2") (pinfunction "S_2") (pintype "passive"))
      (node (ref "T3") (pin "2") (pinfunction "S_2") (pintype "passive"))
      (node (ref "TESTR6") (pin "1") (pinfunction "1_1") (pintype "passive"))
      (node (ref "TP5") (pin "TP") (pinfunction "TP_TP") (pintype "input"))
      (node (ref "U$1") (pin "P$5") (pinfunction "+VOUT_P$5") (pintype "bidirectional"))
    )
  )
)
